# LED_KnuckleBuster.net
KiCad netlist of a schematic drawn in EAGLE
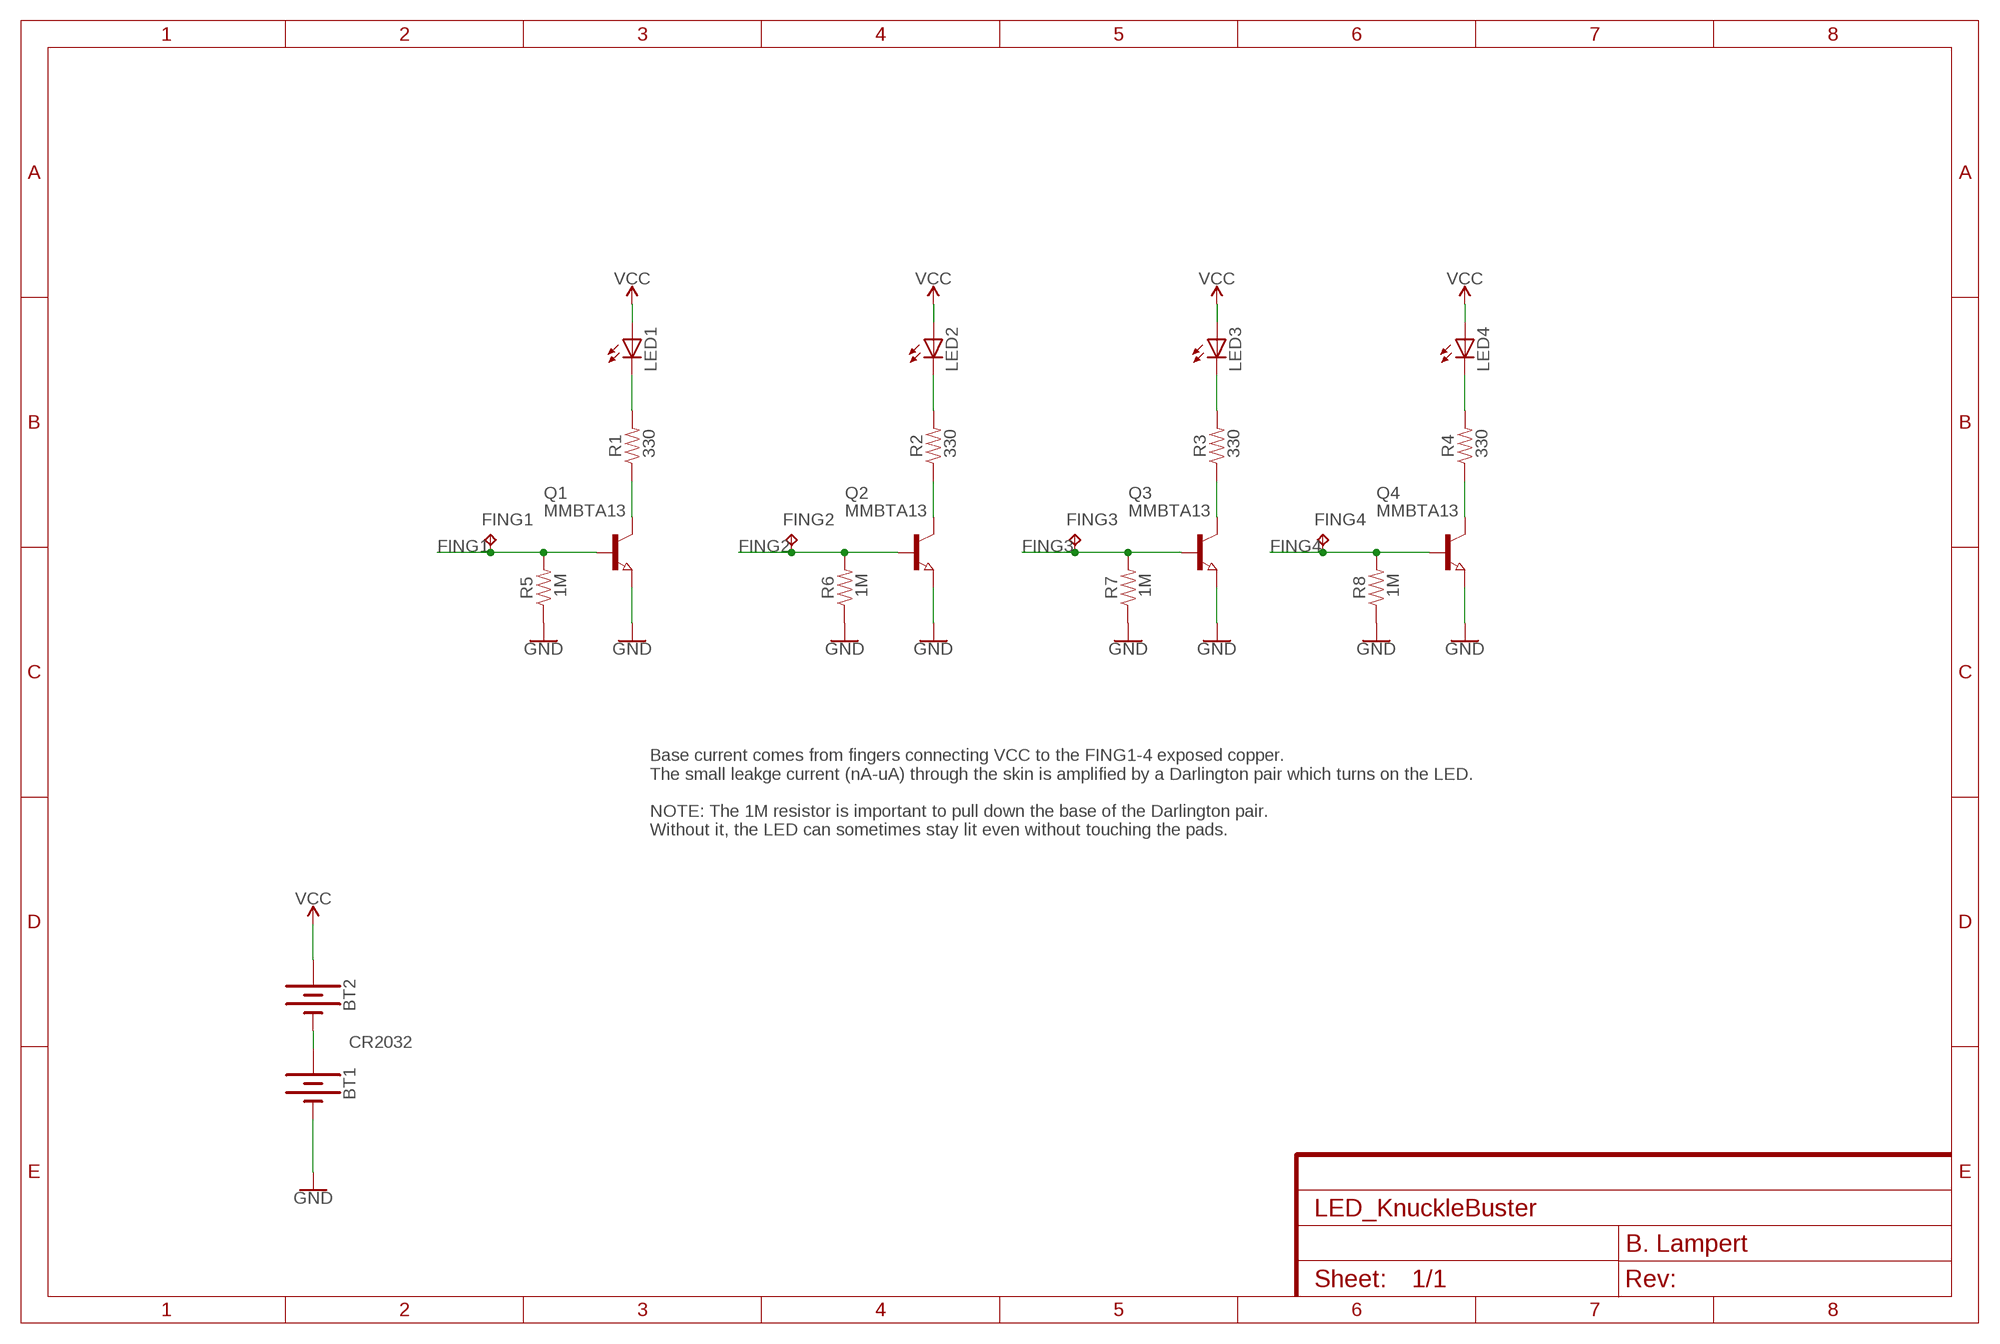
[diagram p0: schematic, sheet 1]

(export (version "E")
  (design (tool "Eeschema 10.0.6"))
  (components
    (comp (ref "BT1")
      (value "BATTERY-20MM_SMD_4LEGS")
      (footprint "eagle-import:BATTCON_20MM_4LEGS")
      (libsource (lib "eagle-import") (part "BATTERY-20MM_SMD_4LEGS"))
    )
    (comp (ref "BT2")
      (value "BATTERY-20MM_SMD_4LEGS")
      (footprint "eagle-import:BATTCON_20MM_4LEGS")
      (libsource (lib "eagle-import") (part "BATTERY-20MM_SMD_4LEGS"))
    )
    (comp (ref "FING1")
      (value "TPB2,54")
      (footprint "eagle-import:B2,54")
      (libsource (lib "eagle-import") (part "TPB2,54"))
    )
    (comp (ref "FING2")
      (value "TPB2,54")
      (footprint "eagle-import:B2,54")
      (libsource (lib "eagle-import") (part "TPB2,54"))
    )
    (comp (ref "FING3")
      (value "TPB2,54")
      (footprint "eagle-import:B2,54")
      (libsource (lib "eagle-import") (part "TPB2,54"))
    )
    (comp (ref "FING4")
      (value "TPB2,54")
      (footprint "eagle-import:B2,54")
      (libsource (lib "eagle-import") (part "TPB2,54"))
    )
    (comp (ref "LED1")
      (value "LEDCHIPLED_0805")
      (footprint "eagle-import:CHIPLED_0805")
      (libsource (lib "eagle-import") (part "LEDCHIPLED_0805"))
    )
    (comp (ref "LED2")
      (value "LEDCHIPLED_0805")
      (footprint "eagle-import:CHIPLED_0805")
      (libsource (lib "eagle-import") (part "LEDCHIPLED_0805"))
    )
    (comp (ref "LED3")
      (value "LEDCHIPLED_0805")
      (footprint "eagle-import:CHIPLED_0805")
      (libsource (lib "eagle-import") (part "LEDCHIPLED_0805"))
    )
    (comp (ref "LED4")
      (value "LEDCHIPLED_0805")
      (footprint "eagle-import:CHIPLED_0805")
      (libsource (lib "eagle-import") (part "LEDCHIPLED_0805"))
    )
    (comp (ref "Q1")
      (value "MMBTA13")
      (footprint "eagle-import:SOT23")
      (libsource (lib "eagle-import") (part "NPN-TRANSISTOR_SOT23"))
    )
    (comp (ref "Q2")
      (value "MMBTA13")
      (footprint "eagle-import:SOT23")
      (libsource (lib "eagle-import") (part "NPN-TRANSISTOR_SOT23"))
    )
    (comp (ref "Q3")
      (value "MMBTA13")
      (footprint "eagle-import:SOT23")
      (libsource (lib "eagle-import") (part "NPN-TRANSISTOR_SOT23"))
    )
    (comp (ref "Q4")
      (value "MMBTA13")
      (footprint "eagle-import:SOT23")
      (libsource (lib "eagle-import") (part "NPN-TRANSISTOR_SOT23"))
    )
    (comp (ref "R1")
      (value "330")
      (footprint "eagle-import:0603")
      (libsource (lib "eagle-import") (part "RESISTOR0603"))
    )
    (comp (ref "R2")
      (value "330")
      (footprint "eagle-import:0603")
      (libsource (lib "eagle-import") (part "RESISTOR0603"))
    )
    (comp (ref "R3")
      (value "330")
      (footprint "eagle-import:0603")
      (libsource (lib "eagle-import") (part "RESISTOR0603"))
    )
    (comp (ref "R4")
      (value "330")
      (footprint "eagle-import:0603")
      (libsource (lib "eagle-import") (part "RESISTOR0603"))
    )
    (comp (ref "R5")
      (value "1M")
      (footprint "eagle-import:0603")
      (libsource (lib "eagle-import") (part "RESISTOR0603"))
    )
    (comp (ref "R6")
      (value "1M")
      (footprint "eagle-import:0603")
      (libsource (lib "eagle-import") (part "RESISTOR0603"))
    )
    (comp (ref "R7")
      (value "1M")
      (footprint "eagle-import:0603")
      (libsource (lib "eagle-import") (part "RESISTOR0603"))
    )
    (comp (ref "R8")
      (value "1M")
      (footprint "eagle-import:0603")
      (libsource (lib "eagle-import") (part "RESISTOR0603"))
    )
  )
  (nets
    (net (code "1") (name "/FING1") (class "Default")
      (node (ref "FING1") (pin "TP") (pinfunction "TP_TP") (pintype "input"))
      (node (ref "Q1") (pin "1") (pinfunction "B_1") (pintype "passive"))
      (node (ref "R5") (pin "2") (pinfunction "2_2") (pintype "passive"))
    )
    (net (code "2") (name "/FING2") (class "Default")
      (node (ref "FING2") (pin "TP") (pinfunction "TP_TP") (pintype "input"))
      (node (ref "Q2") (pin "1") (pinfunction "B_1") (pintype "passive"))
      (node (ref "R6") (pin "2") (pinfunction "2_2") (pintype "passive"))
    )
    (net (code "3") (name "/FING3") (class "Default")
      (node (ref "FING3") (pin "TP") (pinfunction "TP_TP") (pintype "input"))
      (node (ref "Q3") (pin "1") (pinfunction "B_1") (pintype "passive"))
      (node (ref "R7") (pin "2") (pinfunction "2_2") (pintype "passive"))
    )
    (net (code "4") (name "/FING4") (class "Default")
      (node (ref "FING4") (pin "TP") (pinfunction "TP_TP") (pintype "input"))
      (node (ref "Q4") (pin "1") (pinfunction "B_1") (pintype "passive"))
      (node (ref "R8") (pin "2") (pinfunction "2_2") (pintype "passive"))
    )
    (net (code "5") (name "GND") (class "Default")
      (node (ref "BT1") (pin "NEGATIVE") (pinfunction "-_NEGATIVE") (pintype "power_in"))
      (node (ref "Q1") (pin "2") (pinfunction "E_2") (pintype "passive"))
      (node (ref "Q2") (pin "2") (pinfunction "E_2") (pintype "passive"))
      (node (ref "Q3") (pin "2") (pinfunction "E_2") (pintype "passive"))
      (node (ref "Q4") (pin "2") (pinfunction "E_2") (pintype "passive"))
      (node (ref "R5") (pin "1") (pinfunction "1_1") (pintype "passive"))
      (node (ref "R6") (pin "1") (pinfunction "1_1") (pintype "passive"))
      (node (ref "R7") (pin "1") (pinfunction "1_1") (pintype "passive"))
      (node (ref "R8") (pin "1") (pinfunction "1_1") (pintype "passive"))
    )
    (net (code "6") (name "Net-(BT2--)") (class "Default")
      (node (ref "BT1") (pin "POSITIVE@1") (pinfunction "+_POSITIVE@1") (pintype "power_in"))
      (node (ref "BT1") (pin "POSITIVE@2") (pinfunction "+_POSITIVE@2") (pintype "power_in"))
      (node (ref "BT1") (pin "POSITIVE@3") (pinfunction "+_POSITIVE@3") (pintype "power_in"))
      (node (ref "BT1") (pin "POSITIVE@4") (pinfunction "+_POSITIVE@4") (pintype "power_in"))
      (node (ref "BT2") (pin "NEGATIVE") (pinfunction "-_NEGATIVE") (pintype "power_in"))
    )
    (net (code "7") (name "Net-(LED1-PadC)") (class "Default")
      (node (ref "LED1") (pin "C") (pinfunction "C_C") (pintype "passive"))
      (node (ref "R1") (pin "2") (pinfunction "2_2") (pintype "passive"))
    )
    (net (code "8") (name "Net-(LED2-PadC)") (class "Default")
      (node (ref "LED2") (pin "C") (pinfunction "C_C") (pintype "passive"))
      (node (ref "R2") (pin "2") (pinfunction "2_2") (pintype "passive"))
    )
    (net (code "9") (name "Net-(LED3-PadC)") (class "Default")
      (node (ref "LED3") (pin "C") (pinfunction "C_C") (pintype "passive"))
      (node (ref "R3") (pin "2") (pinfunction "2_2") (pintype "passive"))
    )
    (net (code "10") (name "Net-(LED4-PadC)") (class "Default")
      (node (ref "LED4") (pin "C") (pinfunction "C_C") (pintype "passive"))
      (node (ref "R4") (pin "2") (pinfunction "2_2") (pintype "passive"))
    )
    (net (code "11") (name "Net-(Q1-C)") (class "Default")
      (node (ref "Q1") (pin "3") (pinfunction "C_3") (pintype "passive"))
      (node (ref "R1") (pin "1") (pinfunction "1_1") (pintype "passive"))
    )
    (net (code "12") (name "Net-(Q2-C)") (class "Default")
      (node (ref "Q2") (pin "3") (pinfunction "C_3") (pintype "passive"))
      (node (ref "R2") (pin "1") (pinfunction "1_1") (pintype "passive"))
    )
    (net (code "13") (name "Net-(Q3-C)") (class "Default")
      (node (ref "Q3") (pin "3") (pinfunction "C_3") (pintype "passive"))
      (node (ref "R3") (pin "1") (pinfunction "1_1") (pintype "passive"))
    )
    (net (code "14") (name "Net-(Q4-C)") (class "Default")
      (node (ref "Q4") (pin "3") (pinfunction "C_3") (pintype "passive"))
      (node (ref "R4") (pin "1") (pinfunction "1_1") (pintype "passive"))
    )
    (net (code "15") (name "VCC") (class "Default")
      (node (ref "BT2") (pin "POSITIVE@1") (pinfunction "+_POSITIVE@1") (pintype "power_in"))
      (node (ref "BT2") (pin "POSITIVE@2") (pinfunction "+_POSITIVE@2") (pintype "power_in"))
      (node (ref "BT2") (pin "POSITIVE@3") (pinfunction "+_POSITIVE@3") (pintype "power_in"))
      (node (ref "BT2") (pin "POSITIVE@4") (pinfunction "+_POSITIVE@4") (pintype "power_in"))
      (node (ref "LED1") (pin "A") (pinfunction "A_A") (pintype "passive"))
      (node (ref "LED2") (pin "A") (pinfunction "A_A") (pintype "passive"))
      (node (ref "LED3") (pin "A") (pinfunction "A_A") (pintype "passive"))
      (node (ref "LED4") (pin "A") (pinfunction "A_A") (pintype "passive"))
    )
  )
)
